# Audio_Det.net
KiCad netlist of a schematic drawn in Altium Designer
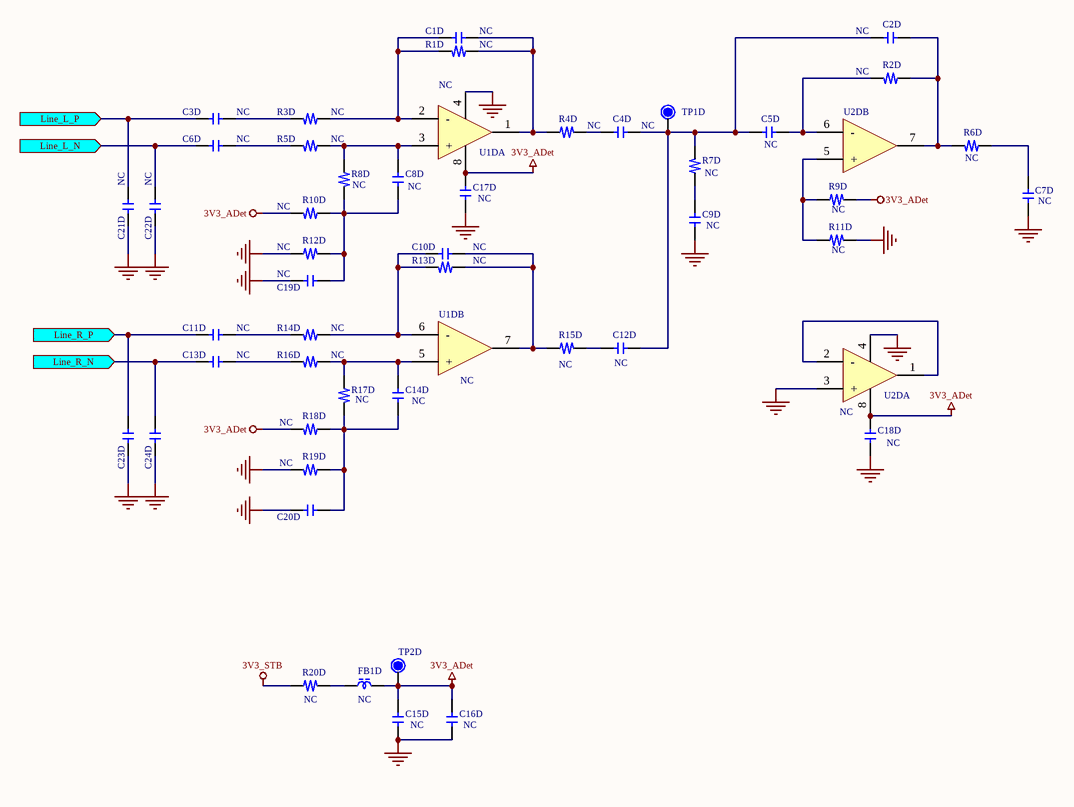
[diagram p0: Audio_Det.SchDoc]

(export (version "E")
  (design (tool "Eeschema 10.0.6"))
  (components
    (comp (ref "C1D")
      (value "47pF")
      (footprint "C0603X80")
      (description "PSHF SMD M CAP 47pF 50V ±5% 0603 NPO")
      (fields (field (name "MANUFACTURER") "Multi Sourced") (field (name "TOLERANCE") "±5%"))
      (libsource (lib "altium-import") (part "root_2_CAP1_"))
    )
    (comp (ref "C2D")
      (value "4.7uF")
      (footprint "C0603X100")
      (description "PSHF SMD M CAP 4.7nF 50V ±10% 0603 X7R")
      (fields (field (name "MANUFACTURER") "Multi Sourced") (field (name "TOLERANCE") "±10%"))
      (libsource (lib "altium-import") (part "root_2_CAP1_"))
    )
    (comp (ref "C3D")
      (value "100nF")
      (footprint "C0603X100")
      (description "GPHF SMD M CAP 100nF 25V ±10% 0603 X7R")
      (fields (field (name "MANUFACTURER") "Multi Sourced") (field (name "TOLERANCE") "±10%"))
      (libsource (lib "altium-import") (part "root_2_CAP1_"))
    )
    (comp (ref "C4D")
      (value "470nF")
      (footprint "C0603X100")
      (description "PSHF SMD M CAP 470nF 25V ±10% 0603 X7R")
      (fields (field (name "MANUFACTURER") "Multi Sourced") (field (name "TOLERANCE") "±10%"))
      (libsource (lib "altium-import") (part "root_2_CAP1_"))
    )
    (comp (ref "C5D")
      (value "150nF")
      (footprint "C0603X100")
      (description "PSHF SMD M CAP 150nF 25V ±10% 0603 X7R")
      (fields (field (name "MANUFACTURER") "Multi Sourced") (field (name "TOLERANCE") "±10%"))
      (libsource (lib "altium-import") (part "root_2_CAP1_"))
    )
    (comp (ref "C6D")
      (value "100nF")
      (footprint "C0603X100")
      (description "GPHF SMD M CAP 100nF 25V ±10% 0603 X7R")
      (fields (field (name "MANUFACTURER") "Multi Sourced") (field (name "TOLERANCE") "±10%"))
      (libsource (lib "altium-import") (part "root_2_CAP1_"))
    )
    (comp (ref "C7D")
      (value "10nF")
      (footprint "C0603X100")
      (description "PSHF SMD M CAP 10nF 50V ±10% 0603 X7R")
      (fields (field (name "MANUFACTURER") "Multi Sourced") (field (name "TOLERANCE") "±10%"))
      (libsource (lib "altium-import") (part "root_3_CAP1_"))
    )
    (comp (ref "C8D")
      (value "47pF")
      (footprint "C0603X80")
      (description "PSHF SMD M CAP 47pF 50V ±5% 0603 NPO")
      (fields (field (name "MANUFACTURER") "Multi Sourced") (field (name "TOLERANCE") "±5%"))
      (libsource (lib "altium-import") (part "root_1_CAP1_"))
    )
    (comp (ref "C9D")
      (value "10uF")
      (footprint "C0805_145")
      (description "PSHF SMD M CAP 10uF 16V ±10% 0805 X7R")
      (fields (field (name "MANUFACTURER") "Multi Sourced") (field (name "TOLERANCE") "±10%"))
      (libsource (lib "altium-import") (part "root_3_CAP1_"))
    )
    (comp (ref "C10D")
      (value "47pF")
      (footprint "C0603X80")
      (description "PSHF SMD M CAP 47pF 50V ±5% 0603 NPO")
      (fields (field (name "MANUFACTURER") "Multi Sourced") (field (name "TOLERANCE") "±5%"))
      (libsource (lib "altium-import") (part "root_2_CAP1_"))
    )
    (comp (ref "C11D")
      (value "100nF")
      (footprint "C0603X100")
      (description "GPHF SMD M CAP 100nF 25V ±10% 0603 X7R")
      (fields (field (name "MANUFACTURER") "Multi Sourced") (field (name "TOLERANCE") "±10%"))
      (libsource (lib "altium-import") (part "root_2_CAP1_"))
    )
    (comp (ref "C12D")
      (value "470nF")
      (footprint "C0603X100")
      (description "PSHF SMD M CAP 470nF 25V ±10% 0603 X7R")
      (fields (field (name "MANUFACTURER") "Multi Sourced") (field (name "TOLERANCE") "±10%"))
      (libsource (lib "altium-import") (part "root_2_CAP1_"))
    )
    (comp (ref "C13D")
      (value "100nF")
      (footprint "C0603X100")
      (description "GPHF SMD M CAP 100nF 25V ±10% 0603 X7R")
      (fields (field (name "MANUFACTURER") "Multi Sourced") (field (name "TOLERANCE") "±10%"))
      (libsource (lib "altium-import") (part "root_2_CAP1_"))
    )
    (comp (ref "C14D")
      (value "47pF")
      (footprint "C0603X80")
      (description "PSHF SMD M CAP 47pF 50V ±5% 0603 NPO")
      (fields (field (name "MANUFACTURER") "Multi Sourced") (field (name "TOLERANCE") "±5%"))
      (libsource (lib "altium-import") (part "root_1_CAP1_"))
    )
    (comp (ref "C15D")
      (value "10uF")
      (footprint "C0805_145")
      (description "PSHF SMD M CAP 10uF 16V ±10% 0805 X7R")
      (fields (field (name "MANUFACTURER") "Multi Sourced") (field (name "TOLERANCE") "±10%"))
      (libsource (lib "altium-import") (part "root_1_CAP1_"))
    )
    (comp (ref "C16D")
      (value "100nF")
      (footprint "C0603X100")
      (description "PSHF SMD M CAP 100nF 25V ±10% 0603 X7R")
      (fields (field (name "MANUFACTURER") "Multi Sourced") (field (name "TOLERANCE") "±10%"))
      (libsource (lib "altium-import") (part "root_3_CAP1_"))
    )
    (comp (ref "C17D")
      (value "100nF")
      (footprint "C0603X100")
      (description "PSHF SMD M CAP 100nF 25V ±10% 0603 X7R")
      (fields (field (name "MANUFACTURER") "Multi Sourced") (field (name "TOLERANCE") "±10%"))
      (libsource (lib "altium-import") (part "root_3_CAP1_"))
    )
    (comp (ref "C18D")
      (value "100nF")
      (footprint "C0603X100")
      (description "PSHF SMD M CAP 100nF 25V ±10% 0603 X7R")
      (fields (field (name "MANUFACTURER") "Multi Sourced") (field (name "TOLERANCE") "±10%"))
      (libsource (lib "altium-import") (part "root_3_CAP1_"))
    )
    (comp (ref "C19D")
      (value "4.7uF")
      (footprint "C0603X105")
      (description "GPHF SMD M CAP 4.7uF 16V ±10% 0603 X5R")
      (fields (field (name "MANUFACTURER") "Multi Sourced") (field (name "TOLERANCE") "±10%"))
      (libsource (lib "altium-import") (part "root_2_CAP1_"))
    )
    (comp (ref "C20D")
      (value "4.7uF")
      (footprint "C0603X105")
      (description "GPHF SMD M CAP 4.7uF 16V ±10% 0603 X5R")
      (fields (field (name "MANUFACTURER") "Multi Sourced") (field (name "TOLERANCE") "±10%"))
      (libsource (lib "altium-import") (part "root_2_CAP1_"))
    )
    (comp (ref "C21D")
      (value "470pF")
      (footprint "C0603X80")
      (description "GPHF SMD CAP 470pF 50V 10%")
      (fields (field (name "MANUFACTURER") "Multi Sourced") (field (name "TOLERANCE") "±10%"))
      (libsource (lib "altium-import") (part "root_3_CAP1_"))
    )
    (comp (ref "C22D")
      (value "470pF")
      (footprint "C0603X80")
      (description "GPHF SMD CAP 470pF 50V 10%")
      (fields (field (name "MANUFACTURER") "Multi Sourced") (field (name "TOLERANCE") "±10%"))
      (libsource (lib "altium-import") (part "root_3_CAP1_"))
    )
    (comp (ref "C23D")
      (value "470pF")
      (footprint "C0603X80")
      (description "GPHF SMD CAP 470pF 50V 10%")
      (fields (field (name "MANUFACTURER") "Multi Sourced") (field (name "TOLERANCE") "±10%"))
      (libsource (lib "altium-import") (part "root_3_CAP1_"))
    )
    (comp (ref "C24D")
      (value "470pF")
      (footprint "C0603X80")
      (description "GPHF SMD CAP 470pF 50V 10%")
      (fields (field (name "MANUFACTURER") "Multi Sourced") (field (name "TOLERANCE") "±10%"))
      (libsource (lib "altium-import") (part "root_3_CAP1_"))
    )
    (comp (ref "FB1D")
      (value "600R")
      (footprint "L0603")
      (description "PS SMD FERRITE BEAD 600OHM 25% 0603")
      (fields (field (name "MANUFACTURER") "[TSA]") (field (name "TOLERANCE") "1:25%"))
      (libsource (lib "altium-import") (part "root_0_Bead1_"))
    )
    (comp (ref "R1D")
      (value "10k")
      (footprint "R0603")
      (description "GPHF SMD RES. 10KOHM 1/10W 1% 0603")
      (fields (field (name "TOLERANCE") "1%") (field (name "MANUFACTURER") "Multi-Sourced"))
      (libsource (lib "altium-import") (part "root_0_RES1_"))
    )
    (comp (ref "R2D")
      (value "680k")
      (footprint "R0603")
      (description "PS SMD RES. 680KOHM 1/10W 5% 0603")
      (fields (field (name "TOLERANCE") "1%") (field (name "MANUFACTURER") "Multi-Sourced"))
      (libsource (lib "altium-import") (part "root_0_RES1_"))
    )
    (comp (ref "R3D")
      (value "10k")
      (footprint "R0603")
      (description "GPHF SMD RES. 10KOHM 1/10W 1% 0603")
      (fields (field (name "TOLERANCE") "1%") (field (name "MANUFACTURER") "Multi-Sourced"))
      (libsource (lib "altium-import") (part "root_0_RES1_"))
    )
    (comp (ref "R4D")
      (value "15R")
      (footprint "R0603")
      (description "PS SMD RES. 15OHM 1/10W 5% 0603")
      (fields (field (name "TOLERANCE") "1%") (field (name "MANUFACTURER") "Multi-Sourced"))
      (libsource (lib "altium-import") (part "root_2_RES1_"))
    )
    (comp (ref "R5D")
      (value "10k")
      (footprint "R0603")
      (description "GPHF SMD RES. 10KOHM 1/10W 1% 0603")
      (fields (field (name "TOLERANCE") "1%") (field (name "MANUFACTURER") "Multi-Sourced"))
      (libsource (lib "altium-import") (part "root_0_RES1_"))
    )
    (comp (ref "R6D")
      (value "560R")
      (footprint "R0603")
      (description "PS SMD RES. 560OHM 1/10W 1% 0603")
      (fields (field (name "TOLERANCE") "1%") (field (name "MANUFACTURER") "Multi-Sourced"))
      (libsource (lib "altium-import") (part "root_0_RES1_"))
    )
    (comp (ref "R7D")
      (value "1.5k")
      (footprint "R0603")
      (description "PS SMD RES. 1.5KOHM 1/10W 1% 0603")
      (fields (field (name "TOLERANCE") "1%") (field (name "MANUFACTURER") "Multi-Sourced"))
      (libsource (lib "altium-import") (part "root_3_RES1_"))
    )
    (comp (ref "R8D")
      (value "10k")
      (footprint "R0603")
      (description "GPHF SMD RES. 10KOHM 1/10W 1% 0603")
      (fields (field (name "TOLERANCE") "1%") (field (name "MANUFACTURER") "Multi-Sourced"))
      (libsource (lib "altium-import") (part "root_1_RES1_"))
    )
    (comp (ref "R9D")
      (value "100k")
      (footprint "R0603")
      (description "PS SMD RES. 100KOHM 1/10W 1% 0603")
      (fields (field (name "TOLERANCE") "1%") (field (name "MANUFACTURER") "Multi-Sourced"))
      (libsource (lib "altium-import") (part "root_2_RES1_"))
    )
    (comp (ref "R10D")
      (value "33k")
      (footprint "R0603")
      (description "PS SMD RES. 33KOHM 1/10W 1% 0603")
      (fields (field (name "TOLERANCE") "1%") (field (name "MANUFACTURER") "Multi-Sourced"))
      (libsource (lib "altium-import") (part "root_0_RES1_"))
    )
    (comp (ref "R11D")
      (value "100k")
      (footprint "R0603")
      (description "PS SMD RES. 100KOHM 1/10W 1% 0603")
      (fields (field (name "TOLERANCE") "1%") (field (name "MANUFACTURER") "Multi-Sourced"))
      (libsource (lib "altium-import") (part "root_2_RES1_"))
    )
    (comp (ref "R12D")
      (value "33k")
      (footprint "R0603")
      (description "PS SMD RES. 33KOHM 1/10W 1% 0603")
      (fields (field (name "TOLERANCE") "1%") (field (name "MANUFACTURER") "Multi-Sourced"))
      (libsource (lib "altium-import") (part "root_2_RES1_"))
    )
    (comp (ref "R13D")
      (value "10k")
      (footprint "R0603")
      (description "GPHF SMD RES. 10KOHM 1/10W 1% 0603")
      (fields (field (name "TOLERANCE") "1%") (field (name "MANUFACTURER") "Multi-Sourced"))
      (libsource (lib "altium-import") (part "root_0_RES1_"))
    )
    (comp (ref "R14D")
      (value "10k")
      (footprint "R0603")
      (description "GPHF SMD RES. 10KOHM 1/10W 1% 0603")
      (fields (field (name "TOLERANCE") "1%") (field (name "MANUFACTURER") "Multi-Sourced"))
      (libsource (lib "altium-import") (part "root_0_RES1_"))
    )
    (comp (ref "R15D")
      (value "15R")
      (footprint "R0603")
      (description "PS SMD RES. 15OHM 1/10W 5% 0603")
      (fields (field (name "TOLERANCE") "1%") (field (name "MANUFACTURER") "Multi-Sourced"))
      (libsource (lib "altium-import") (part "root_2_RES1_"))
    )
    (comp (ref "R16D")
      (value "10k")
      (footprint "R0603")
      (description "GPHF SMD RES. 10KOHM 1/10W 1% 0603")
      (fields (field (name "TOLERANCE") "1%") (field (name "MANUFACTURER") "Multi-Sourced"))
      (libsource (lib "altium-import") (part "root_0_RES1_"))
    )
    (comp (ref "R17D")
      (value "10k")
      (footprint "R0603")
      (description "GPHF SMD RES. 10KOHM 1/10W 1% 0603")
      (fields (field (name "TOLERANCE") "1%") (field (name "MANUFACTURER") "Multi-Sourced"))
      (libsource (lib "altium-import") (part "root_1_RES1_"))
    )
    (comp (ref "R18D")
      (value "33k")
      (footprint "R0603")
      (description "PS SMD RES. 33KOHM 1/10W 1% 0603")
      (fields (field (name "TOLERANCE") "1%") (field (name "MANUFACTURER") "Multi-Sourced"))
      (libsource (lib "altium-import") (part "root_0_RES1_"))
    )
    (comp (ref "R19D")
      (value "33k")
      (footprint "R0603")
      (description "PS SMD RES. 33KOHM 1/10W 1% 0603")
      (fields (field (name "TOLERANCE") "1%") (field (name "MANUFACTURER") "Multi-Sourced"))
      (libsource (lib "altium-import") (part "root_0_RES1_"))
    )
    (comp (ref "R20D")
      (value "2.2R")
      (footprint "R0805")
      (description "PS SMD RES. 2.2OHM 1/8W 1% 0805")
      (fields (field (name "TOLERANCE") "1%") (field (name "MANUFACTURER") "Multi-Sourced"))
      (libsource (lib "altium-import") (part "root_2_RES1_"))
    )
    (comp (ref "TP1D")
      (value "TP")
      (footprint "TP060")
      (description "Test Point")
      (libsource (lib "altium-import") (part "root_1_TP_"))
    )
    (comp (ref "TP2D")
      (value "TP")
      (footprint "TP060")
      (description "Test Point")
      (libsource (lib "altium-import") (part "root_1_TP_"))
    )
    (comp (ref "U1D")
      (value "~")
      (footprint "VSSOP8")
      (description "SMD IC 8P MSOP SGM358YMS SGMICRO")
      (fields (field (name "MANUFACTURER") "SGMICRO") (field (name "PART_NUMBER") "SGM358YMS"))
      (libsource (lib "altium-import") (part "root_2_mirrored_OP_DUAL_"))
    )
    (comp (ref "U2D")
      (value "~")
      (footprint "VSSOP8")
      (description "SMD IC 8P MSOP SGM358YMS SGMICRO")
      (fields (field (name "MANUFACTURER") "SGMICRO") (field (name "PART_NUMBER") "SGM358YMS"))
      (libsource (lib "altium-import") (part "root_2_mirrored_OP_DUAL_"))
    )
  )
  (nets
    (net (code "1") (name "/Line_L_N") (class "Default")
      (node (ref "C22D") (pin "1") (pinfunction "1_1") (pintype "passive"))
      (node (ref "C6D") (pin "2") (pinfunction "2_2") (pintype "passive"))
    )
    (net (code "2") (name "/Line_L_P") (class "Default")
      (node (ref "C21D") (pin "1") (pinfunction "1_1") (pintype "passive"))
      (node (ref "C3D") (pin "2") (pinfunction "2_2") (pintype "passive"))
    )
    (net (code "3") (name "/Line_R_N") (class "Default")
      (node (ref "C13D") (pin "2") (pinfunction "2_2") (pintype "passive"))
      (node (ref "C24D") (pin "1") (pinfunction "1_1") (pintype "passive"))
    )
    (net (code "4") (name "/Line_R_P") (class "Default")
      (node (ref "C11D") (pin "2") (pinfunction "2_2") (pintype "passive"))
      (node (ref "C23D") (pin "1") (pinfunction "1_1") (pintype "passive"))
    )
    (net (code "5") (name "3V3_ADet") (class "Default")
      (node (ref "C15D") (pin "2") (pinfunction "2_2") (pintype "passive"))
      (node (ref "C16D") (pin "1") (pinfunction "1_1") (pintype "passive"))
      (node (ref "C17D") (pin "1") (pinfunction "1_1") (pintype "passive"))
      (node (ref "C18D") (pin "1") (pinfunction "1_1") (pintype "passive"))
      (node (ref "FB1D") (pin "2") (pinfunction "2_2") (pintype "passive"))
      (node (ref "R10D") (pin "1") (pinfunction "1_1") (pintype "passive"))
      (node (ref "R18D") (pin "1") (pinfunction "1_1") (pintype "passive"))
      (node (ref "R9D") (pin "1") (pinfunction "1_1") (pintype "passive"))
      (node (ref "TP2D") (pin "1") (pinfunction "1_1") (pintype "passive"))
      (node (ref "U1D") (pin "8") (pinfunction "+V_8") (pintype "passive"))
      (node (ref "U2D") (pin "8") (pinfunction "+V_8") (pintype "passive"))
    )
    (net (code "6") (name "3V3_STB") (class "Default")
      (node (ref "R20D") (pin "2") (pinfunction "2_2") (pintype "passive"))
    )
    (net (code "7") (name "GND") (class "Default")
      (node (ref "C15D") (pin "1") (pinfunction "1_1") (pintype "passive"))
      (node (ref "C16D") (pin "2") (pinfunction "2_2") (pintype "passive"))
      (node (ref "C17D") (pin "2") (pinfunction "2_2") (pintype "passive"))
      (node (ref "C18D") (pin "2") (pinfunction "2_2") (pintype "passive"))
      (node (ref "C19D") (pin "2") (pinfunction "2_2") (pintype "passive"))
      (node (ref "C20D") (pin "2") (pinfunction "2_2") (pintype "passive"))
      (node (ref "C21D") (pin "2") (pinfunction "2_2") (pintype "passive"))
      (node (ref "C22D") (pin "2") (pinfunction "2_2") (pintype "passive"))
      (node (ref "C23D") (pin "2") (pinfunction "2_2") (pintype "passive"))
      (node (ref "C24D") (pin "2") (pinfunction "2_2") (pintype "passive"))
      (node (ref "C7D") (pin "2") (pinfunction "2_2") (pintype "passive"))
      (node (ref "C9D") (pin "2") (pinfunction "2_2") (pintype "passive"))
      (node (ref "R11D") (pin "1") (pinfunction "1_1") (pintype "passive"))
      (node (ref "R12D") (pin "2") (pinfunction "2_2") (pintype "passive"))
      (node (ref "R19D") (pin "1") (pinfunction "1_1") (pintype "passive"))
      (node (ref "U1D") (pin "4") (pinfunction "-V_4") (pintype "passive"))
      (node (ref "U2D") (pin "3") (pinfunction "+_3") (pintype "passive"))
      (node (ref "U2D") (pin "4") (pinfunction "-V_4") (pintype "passive"))
    )
    (net (code "8") (name "Net-(C3D-Pad1)") (class "Default")
      (node (ref "C3D") (pin "1") (pinfunction "1_1") (pintype "passive"))
      (node (ref "R3D") (pin "1") (pinfunction "1_1") (pintype "passive"))
    )
    (net (code "9") (name "Net-(C4D-Pad2)") (class "Default")
      (node (ref "C4D") (pin "2") (pinfunction "2_2") (pintype "passive"))
      (node (ref "R4D") (pin "1") (pinfunction "1_1") (pintype "passive"))
    )
    (net (code "10") (name "Net-(C6D-Pad1)") (class "Default")
      (node (ref "C6D") (pin "1") (pinfunction "1_1") (pintype "passive"))
      (node (ref "R5D") (pin "1") (pinfunction "1_1") (pintype "passive"))
    )
    (net (code "11") (name "Net-(C7D-Pad1)") (class "Default")
      (node (ref "C7D") (pin "1") (pinfunction "1_1") (pintype "passive"))
      (node (ref "R6D") (pin "2") (pinfunction "2_2") (pintype "passive"))
    )
    (net (code "12") (name "Net-(C9D-Pad1)") (class "Default")
      (node (ref "C9D") (pin "1") (pinfunction "1_1") (pintype "passive"))
      (node (ref "R7D") (pin "2") (pinfunction "2_2") (pintype "passive"))
    )
    (net (code "13") (name "Net-(C11D-Pad1)") (class "Default")
      (node (ref "C11D") (pin "1") (pinfunction "1_1") (pintype "passive"))
      (node (ref "R14D") (pin "1") (pinfunction "1_1") (pintype "passive"))
    )
    (net (code "14") (name "Net-(C12D-Pad1)") (class "Default")
      (node (ref "C12D") (pin "1") (pinfunction "1_1") (pintype "passive"))
      (node (ref "C2D") (pin "2") (pinfunction "2_2") (pintype "passive"))
      (node (ref "C4D") (pin "1") (pinfunction "1_1") (pintype "passive"))
      (node (ref "C5D") (pin "2") (pinfunction "2_2") (pintype "passive"))
      (node (ref "R7D") (pin "1") (pinfunction "1_1") (pintype "passive"))
      (node (ref "TP1D") (pin "1") (pinfunction "1_1") (pintype "passive"))
    )
    (net (code "15") (name "Net-(C12D-Pad2)") (class "Default")
      (node (ref "C12D") (pin "2") (pinfunction "2_2") (pintype "passive"))
      (node (ref "R15D") (pin "1") (pinfunction "1_1") (pintype "passive"))
    )
    (net (code "16") (name "Net-(C13D-Pad1)") (class "Default")
      (node (ref "C13D") (pin "1") (pinfunction "1_1") (pintype "passive"))
      (node (ref "R16D") (pin "1") (pinfunction "1_1") (pintype "passive"))
    )
    (net (code "17") (name "Net-(C14D-Pad1)") (class "Default")
      (node (ref "C14D") (pin "1") (pinfunction "1_1") (pintype "passive"))
      (node (ref "C20D") (pin "1") (pinfunction "1_1") (pintype "passive"))
      (node (ref "R17D") (pin "1") (pinfunction "1_1") (pintype "passive"))
      (node (ref "R18D") (pin "2") (pinfunction "2_2") (pintype "passive"))
      (node (ref "R19D") (pin "2") (pinfunction "2_2") (pintype "passive"))
    )
    (net (code "18") (name "Net-(C19D-Pad1)") (class "Default")
      (node (ref "C19D") (pin "1") (pinfunction "1_1") (pintype "passive"))
      (node (ref "C8D") (pin "1") (pinfunction "1_1") (pintype "passive"))
      (node (ref "R10D") (pin "2") (pinfunction "2_2") (pintype "passive"))
      (node (ref "R12D") (pin "1") (pinfunction "1_1") (pintype "passive"))
      (node (ref "R8D") (pin "1") (pinfunction "1_1") (pintype "passive"))
    )
    (net (code "19") (name "Net-(FB1D-Pad1)") (class "Default")
      (node (ref "FB1D") (pin "1") (pinfunction "1_1") (pintype "passive"))
      (node (ref "R20D") (pin "1") (pinfunction "1_1") (pintype "passive"))
    )
    (net (code "20") (name "Net-(U1DA-+)") (class "Default")
      (node (ref "C8D") (pin "2") (pinfunction "2_2") (pintype "passive"))
      (node (ref "R5D") (pin "2") (pinfunction "2_2") (pintype "passive"))
      (node (ref "R8D") (pin "2") (pinfunction "2_2") (pintype "passive"))
      (node (ref "U1D") (pin "3") (pinfunction "+_3") (pintype "passive"))
    )
    (net (code "21") (name "Net-(U1DA--)") (class "Default")
      (node (ref "C1D") (pin "2") (pinfunction "2_2") (pintype "passive"))
      (node (ref "R1D") (pin "1") (pinfunction "1_1") (pintype "passive"))
      (node (ref "R3D") (pin "2") (pinfunction "2_2") (pintype "passive"))
      (node (ref "U1D") (pin "2") (pinfunction "-_2") (pintype "passive"))
    )
    (net (code "22") (name "Net-(U1DA-OUT)") (class "Default")
      (node (ref "C1D") (pin "1") (pinfunction "1_1") (pintype "passive"))
      (node (ref "R1D") (pin "2") (pinfunction "2_2") (pintype "passive"))
      (node (ref "R4D") (pin "2") (pinfunction "2_2") (pintype "passive"))
      (node (ref "U1D") (pin "1") (pinfunction "OUT_1") (pintype "passive"))
    )
    (net (code "23") (name "Net-(U1DB-+)") (class "Default")
      (node (ref "C14D") (pin "2") (pinfunction "2_2") (pintype "passive"))
      (node (ref "R16D") (pin "2") (pinfunction "2_2") (pintype "passive"))
      (node (ref "R17D") (pin "2") (pinfunction "2_2") (pintype "passive"))
      (node (ref "U1D") (pin "5") (pinfunction "+_5") (pintype "passive"))
    )
    (net (code "24") (name "Net-(U1DB--)") (class "Default")
      (node (ref "C10D") (pin "2") (pinfunction "2_2") (pintype "passive"))
      (node (ref "R13D") (pin "1") (pinfunction "1_1") (pintype "passive"))
      (node (ref "R14D") (pin "2") (pinfunction "2_2") (pintype "passive"))
      (node (ref "U1D") (pin "6") (pinfunction "-_6") (pintype "passive"))
    )
    (net (code "25") (name "Net-(U1DB-OUT)") (class "Default")
      (node (ref "C10D") (pin "1") (pinfunction "1_1") (pintype "passive"))
      (node (ref "R13D") (pin "2") (pinfunction "2_2") (pintype "passive"))
      (node (ref "R15D") (pin "2") (pinfunction "2_2") (pintype "passive"))
      (node (ref "U1D") (pin "7") (pinfunction "OUT_7") (pintype "passive"))
    )
    (net (code "26") (name "Net-(U2DA--)") (class "Default")
      (node (ref "U2D") (pin "1") (pinfunction "OUT_1") (pintype "passive"))
      (node (ref "U2D") (pin "2") (pinfunction "-_2") (pintype "passive"))
    )
    (net (code "27") (name "Net-(U2DB-+)") (class "Default")
      (node (ref "R11D") (pin "2") (pinfunction "2_2") (pintype "passive"))
      (node (ref "R9D") (pin "2") (pinfunction "2_2") (pintype "passive"))
      (node (ref "U2D") (pin "5") (pinfunction "+_5") (pintype "passive"))
    )
    (net (code "28") (name "Net-(U2DB--)") (class "Default")
      (node (ref "C5D") (pin "1") (pinfunction "1_1") (pintype "passive"))
      (node (ref "R2D") (pin "1") (pinfunction "1_1") (pintype "passive"))
      (node (ref "U2D") (pin "6") (pinfunction "-_6") (pintype "passive"))
    )
    (net (code "29") (name "Net-(U2DB-OUT)") (class "Default")
      (node (ref "C2D") (pin "1") (pinfunction "1_1") (pintype "passive"))
      (node (ref "R2D") (pin "2") (pinfunction "2_2") (pintype "passive"))
      (node (ref "R6D") (pin "1") (pinfunction "1_1") (pintype "passive"))
      (node (ref "U2D") (pin "7") (pinfunction "OUT_7") (pintype "passive"))
    )
  )
)
